# M5StickSub.net
KiCad netlist of a schematic drawn in EAGLE
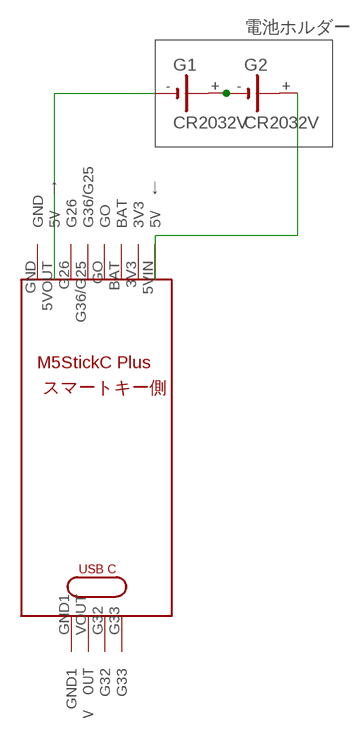
[diagram p0: schematic, sheet 1]

(export (version "E")
  (design (tool "Eeschema 10.0.6"))
  (components
    (comp (ref "G1")
      (value "CR2032V")
      (footprint "eagle-import:CR2032V")
      (libsource (lib "eagle-import") (part "CR2032V"))
    )
    (comp (ref "G2")
      (value "CR2032V")
      (footprint "eagle-import:CR2032V")
      (libsource (lib "eagle-import") (part "CR2032V"))
    )
    (comp (ref "U$1")
      (value "M5STICKCPLUS")
      (footprint "eagle-import:M5STICK")
      (libsource (lib "eagle-import") (part "M5STICKCPLUS"))
    )
  )
  (nets
    (net (code "1") (name "Net-(G1-Pad+)") (class "Default")
      (node (ref "G1") (pin "+") (pinfunction "+_+") (pintype "passive"))
      (node (ref "G2") (pin "-") (pinfunction "-_-") (pintype "passive"))
    )
    (net (code "2") (name "Net-(U$1-5V　←)") (class "Default")
      (node (ref "G2") (pin "+") (pinfunction "+_+") (pintype "passive"))
      (node (ref "U$1") (pin "5VIN") (pinfunction "5V　←_5VIN") (pintype "bidirectional"))
    )
    (net (code "3") (name "Net-(U$1-5V　→)") (class "Default")
      (node (ref "G1") (pin "-") (pinfunction "-_-") (pintype "passive"))
      (node (ref "U$1") (pin "5VOUT") (pinfunction "5V　→_5VOUT") (pintype "bidirectional"))
    )
    (net (code "4") (name "unconnected-(G1-+-Pad+@1)") (class "Default")
      (node (ref "G1") (pin "+@1") (pinfunction "+_+@1") (pintype "passive"))
    )
    (net (code "5") (name "unconnected-(G2-+-Pad+@1)") (class "Default")
      (node (ref "G2") (pin "+@1") (pinfunction "+_+@1") (pintype "passive"))
    )
    (net (code "6") (name "unconnected-(U$1-Pad3V3)") (class "Default")
      (node (ref "U$1") (pin "3V3") (pinfunction "3V3_3V3") (pintype "bidirectional"))
    )
    (net (code "7") (name "unconnected-(U$1-PadBAT)") (class "Default")
      (node (ref "U$1") (pin "BAT") (pinfunction "BAT_BAT") (pintype "bidirectional"))
    )
    (net (code "8") (name "unconnected-(U$1-PadG26)") (class "Default")
      (node (ref "U$1") (pin "G26") (pinfunction "G26_G26") (pintype "bidirectional"))
    )
    (net (code "9") (name "unconnected-(U$1-PadG32)") (class "Default")
      (node (ref "U$1") (pin "G32") (pinfunction "G32_G32") (pintype "bidirectional"))
    )
    (net (code "10") (name "unconnected-(U$1-PadG33)") (class "Default")
      (node (ref "U$1") (pin "G33") (pinfunction "G33_G33") (pintype "bidirectional"))
    )
    (net (code "11") (name "unconnected-(U$1-PadG36{slash}G25)") (class "Default")
      (node (ref "U$1") (pin "G36/G25") (pinfunction "G36/G25_G36/G25") (pintype "bidirectional"))
    )
    (net (code "12") (name "unconnected-(U$1-PadGND)") (class "Default")
      (node (ref "U$1") (pin "GND") (pinfunction "GND_GND") (pintype "bidirectional"))
    )
    (net (code "13") (name "unconnected-(U$1-PadGND1)") (class "Default")
      (node (ref "U$1") (pin "GND1") (pinfunction "GND1_GND1") (pintype "bidirectional"))
    )
    (net (code "14") (name "unconnected-(U$1-PadGO)") (class "Default")
      (node (ref "U$1") (pin "GO") (pinfunction "GO_GO") (pintype "bidirectional"))
    )
    (net (code "15") (name "unconnected-(U$1-V　OUT-PadVOUT)") (class "Default")
      (node (ref "U$1") (pin "VOUT") (pinfunction "V　OUT_VOUT") (pintype "bidirectional"))
    )
  )
)
